# Booster_RF_CH_SUP_CTRL.net
KiCad netlist of a schematic drawn in Altium Designer
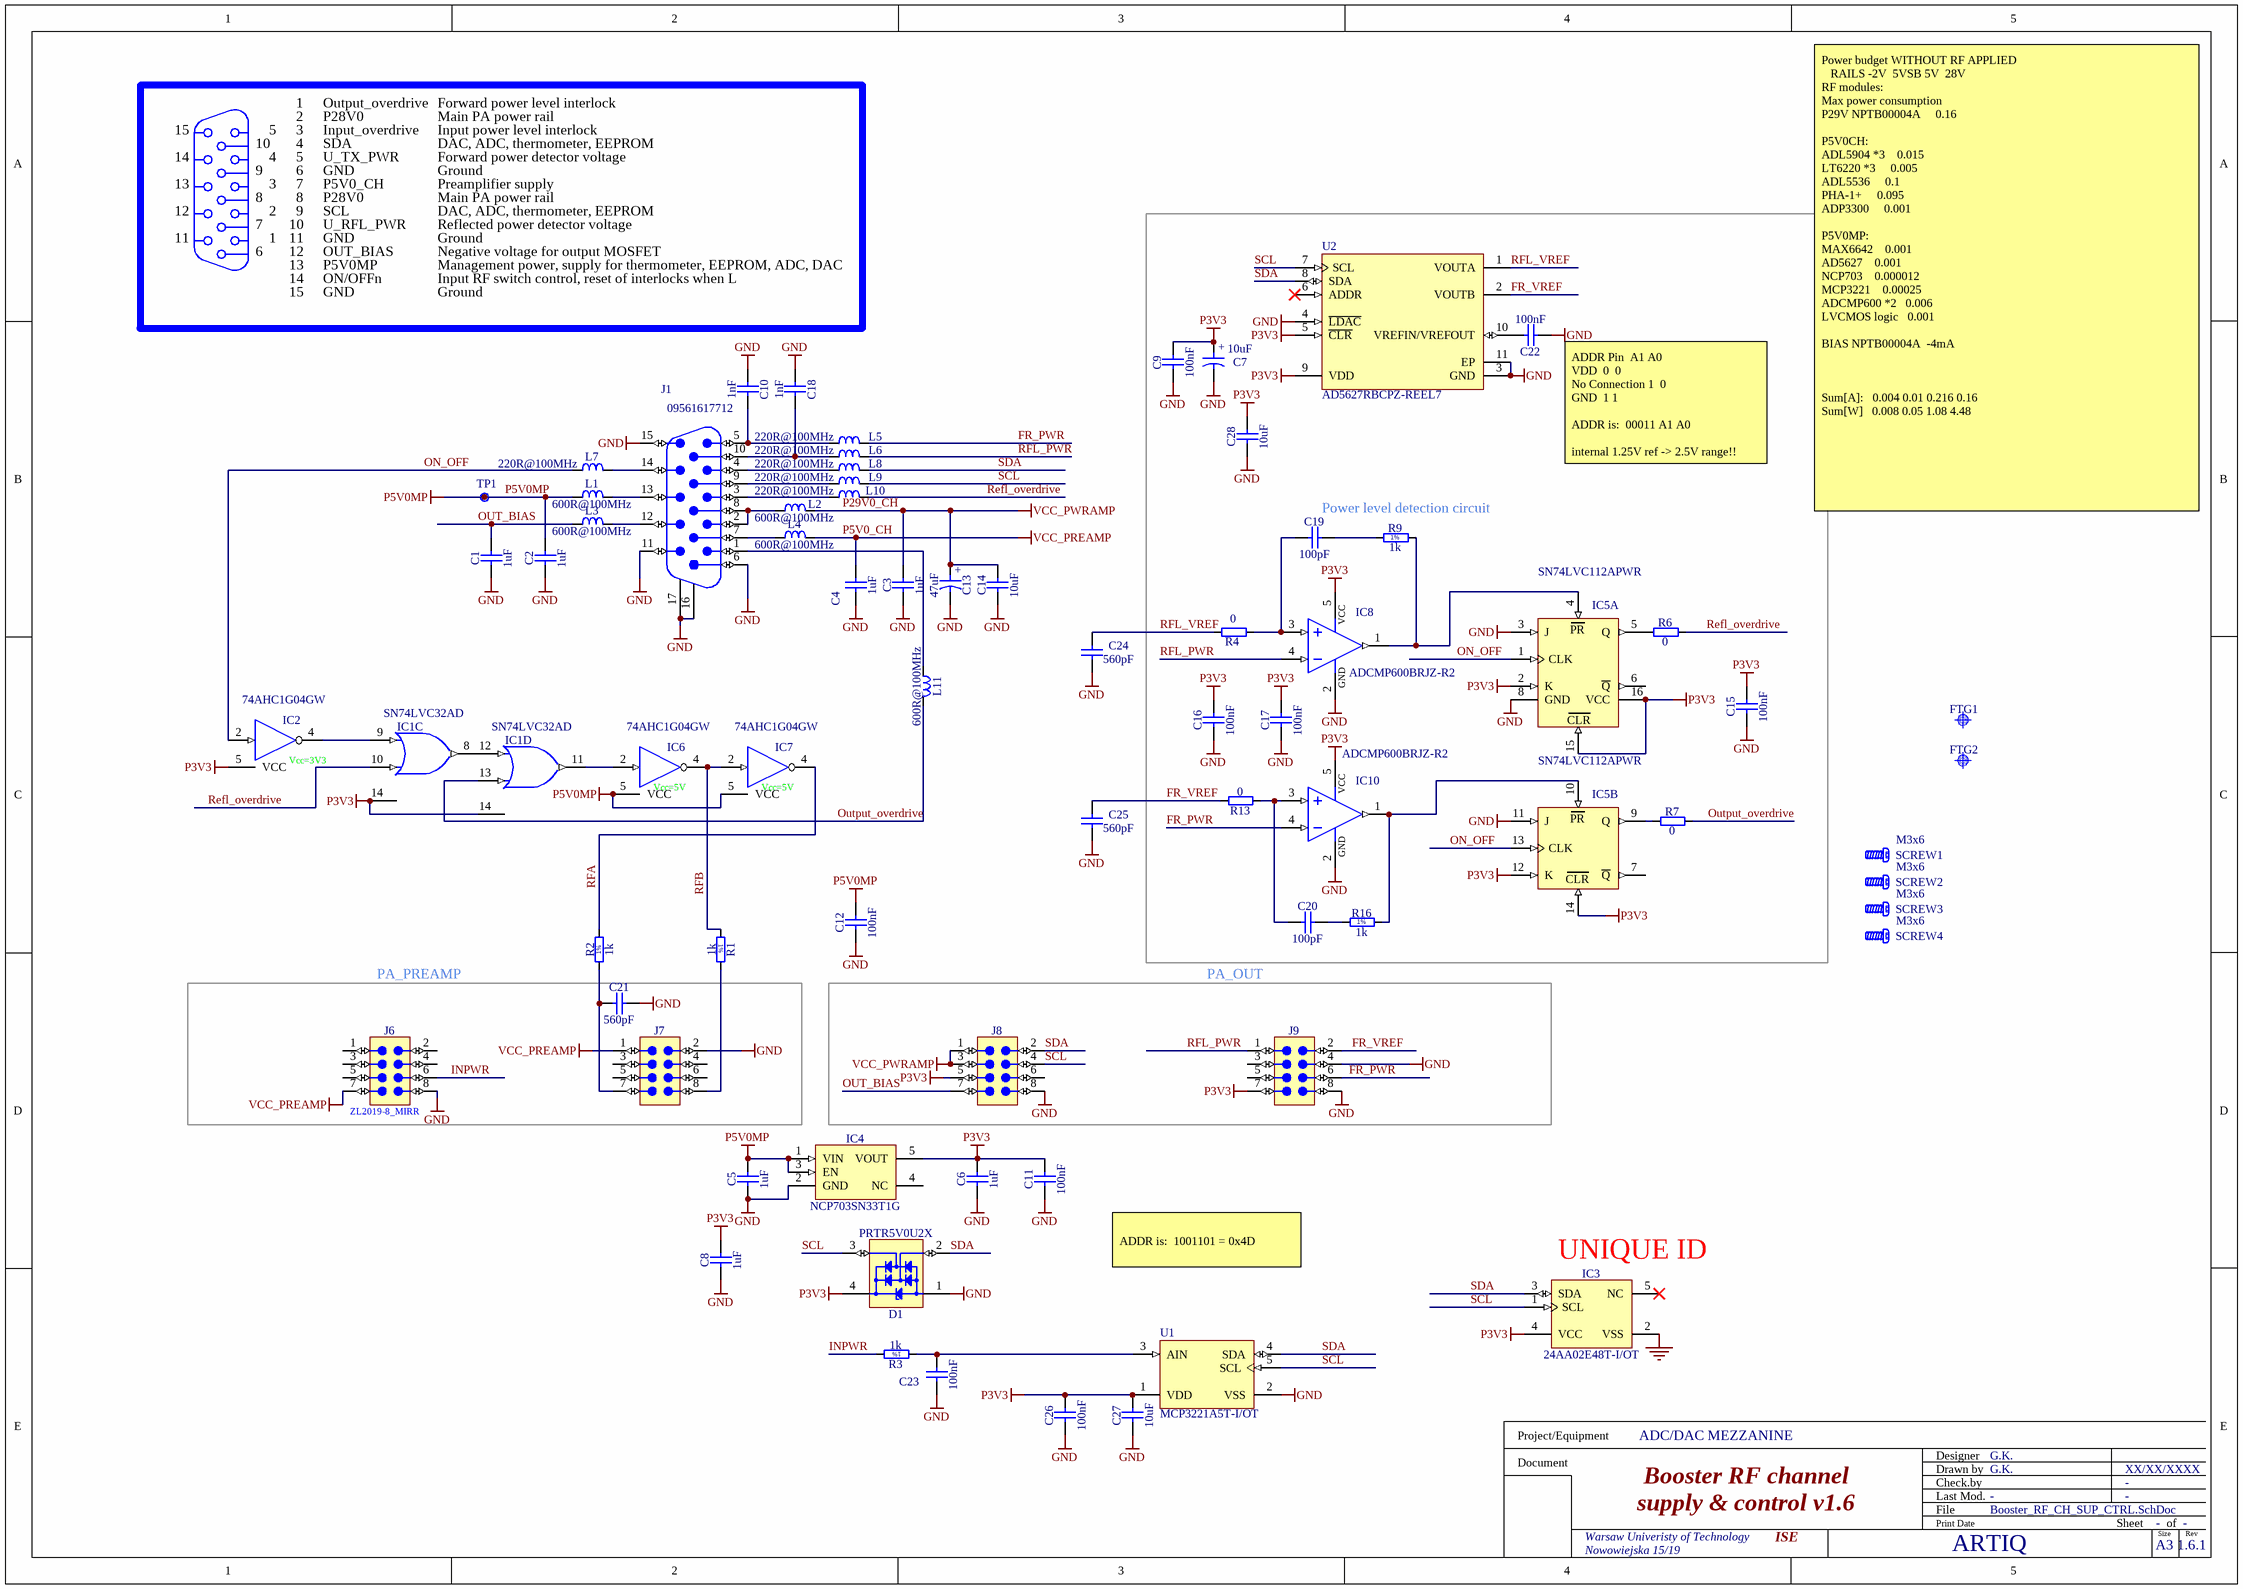
[diagram p0: Booster_RF_CH_SUP_CTRL.SchDoc]

(export (version "E")
  (design (tool "Eeschema 10.0.6"))
  (components
    (comp (ref "C1")
      (value "1uF")
      (footprint "CAPC2012X110N")
      (description "Non-polarised capacitor")
      (fields
        (field (name "PART NUMBER") "CC0805_1UF_50V_10%_X7R")
        (field (name "VOLTAGE") "50V")
        (field (name "AUTHOR") "CERN DEM JLC")
      )
      (libsource (lib "Capacitors") (part "Capacitor - non polarized"))
    )
    (comp (ref "C2")
      (value "1uF")
      (footprint "CAPC2012X110N")
      (description "Non-polarised capacitor")
      (fields
        (field (name "PART NUMBER") "CC0805_1UF_50V_10%_X7R")
        (field (name "VOLTAGE") "50V")
        (field (name "AUTHOR") "CERN DEM JLC")
      )
      (libsource (lib "Capacitors") (part "Capacitor - non polarized"))
    )
    (comp (ref "C3")
      (value "1uF")
      (footprint "CAPC2012X110N")
      (description "Non-polarised capacitor")
      (fields
        (field (name "PART NUMBER") "CC0805_1UF_50V_10%_X7R")
        (field (name "VOLTAGE") "50V")
        (field (name "AUTHOR") "CERN DEM JLC")
      )
      (libsource (lib "Capacitors") (part "Capacitor - non polarized"))
    )
    (comp (ref "C4")
      (value "1uF")
      (footprint "CAPC2012X110N")
      (description "Non-polarised capacitor")
      (fields
        (field (name "PART NUMBER") "CC0805_1UF_50V_10%_X7R")
        (field (name "VOLTAGE") "50V")
        (field (name "AUTHOR") "CERN DEM JLC")
      )
      (libsource (lib "Capacitors") (part "Capacitor - non polarized"))
    )
    (comp (ref "C5")
      (value "1uF")
      (footprint "CAPC2012X140N")
      (description "Non-polarised capacitor")
      (fields
        (field (name "PART NUMBER") "CC0805_1UF_35V_20%_X7R")
        (field (name "VOLTAGE") "35V")
        (field (name "AUTHOR") "CERN DEM JLC")
      )
      (libsource (lib "Capacitors") (part "Capacitor - non polarized"))
    )
    (comp (ref "C6")
      (value "1uF")
      (footprint "CAPC2012X140N")
      (description "Non-polarised capacitor")
      (fields
        (field (name "PART NUMBER") "CC0805_1UF_35V_20%_X7R")
        (field (name "VOLTAGE") "35V")
        (field (name "AUTHOR") "CERN DEM JLC")
      )
      (libsource (lib "Capacitors") (part "Capacitor - non polarized"))
    )
    (comp (ref "C7")
      (value "10uF")
      (footprint "CAPMP3216X180N")
      (description "Polarised capacitor")
      (fields
        (field (name "PART NUMBER") "CTE3216-18_10UF_16V_20%_AVX_TCJ")
        (field (name "VOLTAGE") "16V")
        (field (name "AUTHOR") "CERN DEM JLC")
      )
      (libsource (lib "Capacitors") (part "Capacitor - polarized"))
    )
    (comp (ref "C8")
      (value "1uF")
      (footprint "CAPC2012X140N")
      (description "Non-polarised capacitor")
      (fields
        (field (name "PART NUMBER") "CC0805_1UF_35V_20%_X7R")
        (field (name "VOLTAGE") "35V")
        (field (name "AUTHOR") "CERN DEM JLC")
      )
      (libsource (lib "Capacitors") (part "Capacitor - non polarized"))
    )
    (comp (ref "C9")
      (value "100nF")
      (footprint "CAPC1005X55N")
      (description "Non-polarised capacitor")
      (fields
        (field (name "PART NUMBER") "CC0402_100NF_16V_10%_X5R")
        (field (name "VOLTAGE") "16V")
        (field (name "AUTHOR") "CERN DEM JLC")
      )
      (libsource (lib "Capacitors") (part "Capacitor - non polarized"))
    )
    (comp (ref "C10")
      (value "1nF")
      (footprint "CAPC1608X90N")
      (description "Non-polarised capacitor")
      (fields
        (field (name "PART NUMBER") "CC0603_1NF_50V_5%_NP0")
        (field (name "VOLTAGE") "50V")
        (field (name "AUTHOR") "CERN DEM JLC")
      )
      (libsource (lib "Capacitors") (part "Capacitor - non polarized"))
    )
    (comp (ref "C11")
      (value "100nF")
      (footprint "CAPC1005X55N")
      (description "Non-polarised capacitor")
      (fields
        (field (name "PART NUMBER") "CC0402_100NF_16V_10%_X5R")
        (field (name "VOLTAGE") "16V")
        (field (name "AUTHOR") "CERN DEM JLC")
      )
      (libsource (lib "Capacitors") (part "Capacitor - non polarized"))
    )
    (comp (ref "C12")
      (value "100nF")
      (footprint "CAPC1005X55N")
      (description "Non-polarised capacitor")
      (fields
        (field (name "PART NUMBER") "CC0402_100NF_16V_10%_X5R")
        (field (name "VOLTAGE") "16V")
        (field (name "AUTHOR") "CERN DEM JLC")
      )
      (libsource (lib "Capacitors") (part "Capacitor - non polarized"))
    )
    (comp (ref "C13")
      (value "47uF")
      (footprint "CAPMP7343X430N")
      (description "Polarised capacitor")
      (fields
        (field (name "PART NUMBER") "CTE7343-43_47UF_35V_10%_LESR0300")
        (field (name "VOLTAGE") "35V")
        (field (name "AUTHOR") "CERN DEM JLC")
      )
      (libsource (lib "Capacitors") (part "Capacitor - polarized"))
    )
    (comp (ref "C14")
      (value "10uF")
      (footprint "CAPC3216X190N")
      (description "Non-polarised capacitor")
      (fields
        (field (name "PART NUMBER") "CC1206_10UF_50V_10%_X5R_TDK_CGA5L3X5R1H106K160AB")
        (field (name "VOLTAGE") "50V")
        (field (name "AUTHOR") "CERN DEM BC")
      )
      (libsource (lib "Capacitors") (part "Capacitor - non polarized"))
    )
    (comp (ref "C15")
      (value "100nF")
      (footprint "CAPC1005X55N")
      (description "Non-polarised capacitor")
      (fields
        (field (name "PART NUMBER") "CC0402_100NF_16V_10%_X5R")
        (field (name "VOLTAGE") "16V")
        (field (name "AUTHOR") "CERN DEM JLC")
      )
      (libsource (lib "Capacitors") (part "Capacitor - non polarized"))
    )
    (comp (ref "C16")
      (value "100nF")
      (footprint "CAPC1005X55N")
      (description "Non-polarised capacitor")
      (fields
        (field (name "PART NUMBER") "CC0402_100NF_16V_10%_X5R")
        (field (name "VOLTAGE") "16V")
        (field (name "AUTHOR") "CERN DEM JLC")
      )
      (libsource (lib "Capacitors") (part "Capacitor - non polarized"))
    )
    (comp (ref "C17")
      (value "100nF")
      (footprint "CAPC1005X55N")
      (description "Non-polarised capacitor")
      (fields
        (field (name "PART NUMBER") "CC0402_100NF_16V_10%_X5R")
        (field (name "VOLTAGE") "16V")
        (field (name "AUTHOR") "CERN DEM JLC")
      )
      (libsource (lib "Capacitors") (part "Capacitor - non polarized"))
    )
    (comp (ref "C18")
      (value "1nF")
      (footprint "CAPC1608X90N")
      (description "Non-polarised capacitor")
      (fields
        (field (name "PART NUMBER") "CC0603_1NF_50V_5%_NP0")
        (field (name "VOLTAGE") "50V")
        (field (name "AUTHOR") "CERN DEM JLC")
      )
      (libsource (lib "Capacitors") (part "Capacitor - non polarized"))
    )
    (comp (ref "C19")
      (value "100pF")
      (footprint "CAPC1005X55N")
      (description "Non-polarised capacitor")
      (fields
        (field (name "PART NUMBER") "CC0402_100PF_50V_5%_C0G")
        (field (name "VOLTAGE") "50V")
        (field (name "AUTHOR") "CERN DEM JLC")
      )
      (libsource (lib "Capacitors") (part "Capacitor - non polarized"))
    )
    (comp (ref "C20")
      (value "100pF")
      (footprint "CAPC1005X55N")
      (description "Non-polarised capacitor")
      (fields
        (field (name "PART NUMBER") "CC0402_100PF_50V_5%_C0G")
        (field (name "VOLTAGE") "50V")
        (field (name "AUTHOR") "CERN DEM JLC")
      )
      (libsource (lib "Capacitors") (part "Capacitor - non polarized"))
    )
    (comp (ref "C21")
      (value "560pF")
      (footprint "CAPC1608X87N")
      (description "Non-polarised capacitor")
      (fields
        (field (name "PART NUMBER") "CC0603_560PF_50V_5%_NP0")
        (field (name "VOLTAGE") "50V")
        (field (name "AUTHOR") "CERN DEM JLC")
      )
      (libsource (lib "Capacitors") (part "Capacitor - non polarized"))
    )
    (comp (ref "C22")
      (value "100nF")
      (footprint "CAPC1005X55N")
      (description "Non-polarised capacitor")
      (fields
        (field (name "PART NUMBER") "CC0402_100NF_16V_10%_X5R")
        (field (name "VOLTAGE") "16V")
        (field (name "AUTHOR") "CERN DEM JLC")
      )
      (libsource (lib "Capacitors") (part "Capacitor - non polarized"))
    )
    (comp (ref "C23")
      (value "100nF")
      (footprint "CAPC1005X55N")
      (description "Non-polarised capacitor")
      (fields
        (field (name "PART NUMBER") "CC0402_100NF_16V_10%_X5R")
        (field (name "VOLTAGE") "16V")
        (field (name "AUTHOR") "CERN DEM JLC")
      )
      (libsource (lib "Capacitors") (part "Capacitor - non polarized"))
    )
    (comp (ref "C24")
      (value "560pF")
      (footprint "CAPC1608X87N")
      (description "Non-polarised capacitor")
      (fields
        (field (name "PART NUMBER") "CC0603_560PF_50V_5%_NP0")
        (field (name "VOLTAGE") "50V")
        (field (name "AUTHOR") "CERN DEM JLC")
      )
      (libsource (lib "Capacitors") (part "Capacitor - non polarized"))
    )
    (comp (ref "C25")
      (value "560pF")
      (footprint "CAPC1608X87N")
      (description "Non-polarised capacitor")
      (fields
        (field (name "PART NUMBER") "CC0603_560PF_50V_5%_NP0")
        (field (name "VOLTAGE") "50V")
        (field (name "AUTHOR") "CERN DEM JLC")
      )
      (libsource (lib "Capacitors") (part "Capacitor - non polarized"))
    )
    (comp (ref "C26")
      (value "100nF")
      (footprint "CAPC1005X55N")
      (description "Non-polarised capacitor")
      (fields
        (field (name "PART NUMBER") "CC0402_100NF_16V_10%_X5R")
        (field (name "VOLTAGE") "16V")
        (field (name "AUTHOR") "CERN DEM JLC")
      )
      (libsource (lib "Capacitors") (part "Capacitor - non polarized"))
    )
    (comp (ref "C27")
      (value "10uF")
      (footprint "CAPC3216X190N")
      (description "Non-polarised capacitor")
      (fields
        (field (name "PART NUMBER") "CC1206_10UF_50V_10%_X5R_TDK_CGA5L3X5R1H106K160AB")
        (field (name "VOLTAGE") "50V")
        (field (name "AUTHOR") "CERN DEM BC")
      )
      (libsource (lib "Capacitors") (part "Capacitor - non polarized"))
    )
    (comp (ref "C28")
      (value "10uF")
      (footprint "CAPC3216X190N")
      (description "Non-polarised capacitor")
      (fields
        (field (name "PART NUMBER") "CC1206_10UF_50V_10%_X5R_TDK_CGA5L3X5R1H106K160AB")
        (field (name "VOLTAGE") "50V")
        (field (name "AUTHOR") "CERN DEM BC")
      )
      (libsource (lib "Capacitors") (part "Capacitor - non polarized"))
    )
    (comp (ref "D1")
      (value "PRTR5V0U2X")
      (footprint "SOT190P230X110-4N")
      (description "Ultra Low Capacitance Double Rail-to-Rail ESD Protection Diode")
      (fields
        (field (name "VOLTAGE") "5.5V")
        (field (name "MANUFACTURER") "NXP SEMICONDUCTORS")
        (field (name "AUTHOR") "CERN DEM JLC")
      )
      (libsource (lib "ICs And Semiconductors") (part "PRTR5V0U2X"))
    )
    (comp (ref "FTG1")
      (value "Use only in PCB")
      (footprint "FIDUCIAL_TOP_C100-200")
      (description "Fiducial Target")
      (fields (field (name "PART NUMBER") "FIDUCIAL_TARGET_C100-200") (field (name "AUTHOR") "CERN DEM JLC"))
      (libsource (lib "Eletro-mechanical") (part "Fiducial Target"))
    )
    (comp (ref "FTG2")
      (value "Use only in PCB")
      (footprint "FIDUCIAL_TOP_S100-200")
      (description "Fiducial Target")
      (fields (field (name "PART NUMBER") "FIDUCIAL_TARGET_S100-200") (field (name "AUTHOR") "CERN DEM JLC"))
      (libsource (lib "Eletro-mechanical") (part "Fiducial Target"))
    )
    (comp (ref "IC1")
      (value "SN74LVC32AD")
      (footprint "SOIC127P600X175-14N")
      (description "Quad 2-Input OR Gate")
      (fields (field (name "MANUFACTURER") "TEXAS INSTRUMENTS") (field (name "AUTHOR") "CERN DEM JLC"))
      (libsource (lib "ICs And Semiconductors") (part "7432"))
    )
    (comp (ref "IC2")
      (value "74AHC1G04GW")
      (footprint "SOT65P212X110-5N")
      (description "Single Inverter Buffer")
      (fields (field (name "MANUFACTURER") "NXP SEMICONDUCTORS") (field (name "AUTHOR") "CERN DEM JLC"))
      (libsource (lib "ICs And Semiconductors") (part "741G04"))
    )
    (comp (ref "IC3")
      (value "24AA02E48T-I/OT")
      (footprint "SOT95P280X145-5N")
      (description "1.7V-5.5V, 2K I2C Serial EEPROM With EUI-48 Node Identity")
      (fields (field (name "MANUFACTURER") "MICROCHIP TECHNOLOGY") (field (name "AUTHOR") "CERN DEM MR"))
      (libsource (lib "ICs And Semiconductors") (part "24AA02E48T-I/OT"))
    )
    (comp (ref "IC4")
      (value "NCP703SN33T1G")
      (footprint "SOT95P275X110-5N")
      (description "3.3V 300mA, Ultra-Low Quiescent Current, IQ 12uA, Ultra-Low Noise, LDO Voltage Regulator")
      (fields (field (name "MANUFACTURER") "ON SEMICONDUCTOR") (field (name "AUTHOR") "CERN DEM JLC"))
      (libsource (lib "ICs And Semiconductors") (part "NCP703SN"))
    )
    (comp (ref "IC5")
      (value "SN74LVC112APWR")
      (footprint "SOP65P640X120-16N")
      (description "Dual Negative-Edge-Triggered J-K Flip-Flop With Clear And Preset")
      (fields (field (name "MANUFACTURER") "TEXAS INSTRUMENTS") (field (name "AUTHOR") "CERN DEM JLC"))
      (libsource (lib "ICS-logic") (part "74LVC112APWR"))
    )
    (comp (ref "IC6")
      (value "74AHC1G04GW")
      (footprint "SOT65P212X110-5N")
      (description "Single Inverter Buffer")
      (fields (field (name "MANUFACTURER") "NXP SEMICONDUCTORS") (field (name "AUTHOR") "CERN DEM JLC"))
      (libsource (lib "ICs And Semiconductors") (part "741G04"))
    )
    (comp (ref "IC7")
      (value "74AHC1G04GW")
      (footprint "SOT65P212X110-5N")
      (description "Single Inverter Buffer")
      (fields (field (name "MANUFACTURER") "NXP SEMICONDUCTORS") (field (name "AUTHOR") "CERN DEM JLC"))
      (libsource (lib "ICs And Semiconductors") (part "741G04"))
    )
    (comp (ref "IC8")
      (value "ADCMP600BRJZ-R2")
      (footprint "SOT95P280X145-5N")
      (description "Rail-to-Rail, Very Fast, 2.5 V to 5.5 V Single-Supply TTL/CMOS Comparator")
      (fields (field (name "MANUFACTURER") "ANALOG DEVICES") (field (name "AUTHOR") "CERN DEM JLC"))
      (libsource (lib "ICs And Semiconductors") (part "ADCMP600"))
    )
    (comp (ref "IC10")
      (value "ADCMP600BRJZ-R2")
      (footprint "SOT95P280X145-5N")
      (description "Rail-to-Rail, Very Fast, 2.5 V to 5.5 V Single-Supply TTL/CMOS Comparator")
      (fields (field (name "MANUFACTURER") "ANALOG DEVICES") (field (name "AUTHOR") "CERN DEM JLC"))
      (libsource (lib "ICs And Semiconductors") (part "ADCMP600"))
    )
    (comp (ref "J1")
      (value "HD-Sub")
      (footprint "TYCO_5750489-1")
      (description "Connector High Density D-sub 15 Male")
      (fields
        (field (name "PART NUMBER") "HARTING_09561617712")
        (field (name "MANUFACTURER") "HARTING Elektronik")
        (field (name "MANUFACTURER PART NUMBER") "09561617712")
        (field (name "AUTHOR") "GK")
      )
      (libsource (lib "LIBRARY_SCH") (part "CON_DB15_V_M_5750489-1"))
    )
    (comp (ref "J6")
      (value "Header 8")
      (footprint "ZL2019-8_MIRR")
      (description "Connector 8 Male")
      (fields
        (field (name "PART NUMBER") "ZL2019-8")
        (field (name "MANUFACTURER") "NINIGI")
        (field (name "AUTHOR") "GK")
      )
      (libsource (lib "LIBRARY_SCH") (part "CON_2x4 2.54 male MIRROR"))
    )
    (comp (ref "J7")
      (value "Header 8")
      (footprint "ZL2019-8_MIRR")
      (description "Connector 8 Male")
      (fields
        (field (name "PART NUMBER") "ZL2019-8")
        (field (name "MANUFACTURER") "NINIGI")
        (field (name "AUTHOR") "GK")
      )
      (libsource (lib "LIBRARY_SCH") (part "CON_2x4 2.54 male MIRROR"))
    )
    (comp (ref "J8")
      (value "Header 8")
      (footprint "ZL2019-8_MIRR")
      (description "Connector 8 Male")
      (fields
        (field (name "PART NUMBER") "ZL2019-8")
        (field (name "MANUFACTURER") "NINIGI")
        (field (name "AUTHOR") "GK")
      )
      (libsource (lib "LIBRARY_SCH") (part "CON_2x4 2.54 male MIRROR"))
    )
    (comp (ref "J9")
      (value "Header 8")
      (footprint "ZL2019-8_MIRR")
      (description "Connector 8 Male")
      (fields
        (field (name "PART NUMBER") "ZL2019-8")
        (field (name "MANUFACTURER") "NINIGI")
        (field (name "AUTHOR") "GK")
      )
      (libsource (lib "LIBRARY_SCH") (part "CON_2x4 2.54 male MIRROR"))
    )
    (comp (ref "L1")
      (value "600R@100MHz")
      (footprint "INDC3216X130N")
      (description "Inductor")
      (fields
        (field (name "PART NUMBER") "IND1206_WURTH_74279218")
        (field (name "POWER") "2A")
        (field (name "AUTHOR") "CERN DEM JLC")
      )
      (libsource (lib "Inductors & Transformers") (part "Inductor"))
    )
    (comp (ref "L2")
      (value "600R@100MHz")
      (footprint "INDC3216X130N")
      (description "Inductor")
      (fields
        (field (name "PART NUMBER") "IND1206_WURTH_74279218")
        (field (name "POWER") "2A")
        (field (name "AUTHOR") "CERN DEM JLC")
      )
      (libsource (lib "Inductors & Transformers") (part "Inductor"))
    )
    (comp (ref "L3")
      (value "600R@100MHz")
      (footprint "INDC3216X130N")
      (description "Inductor")
      (fields
        (field (name "PART NUMBER") "IND1206_WURTH_74279218")
        (field (name "POWER") "2A")
        (field (name "AUTHOR") "CERN DEM JLC")
      )
      (libsource (lib "Inductors & Transformers") (part "Inductor"))
    )
    (comp (ref "L4")
      (value "600R@100MHz")
      (footprint "INDC3216X130N")
      (description "Inductor")
      (fields
        (field (name "PART NUMBER") "IND1206_WURTH_74279218")
        (field (name "POWER") "2A")
        (field (name "AUTHOR") "CERN DEM JLC")
      )
      (libsource (lib "Inductors & Transformers") (part "Inductor"))
    )
    (comp (ref "L5")
      (value "220R@100MHz")
      (footprint "INDC1005X55N")
      (description "Inductor")
      (fields
        (field (name "PART NUMBER") "IND0402_MURATA_BLM15HB221SN1")
        (field (name "POWER") "250mA")
        (field (name "AUTHOR") "CERN DEM JLC")
      )
      (libsource (lib "Inductors & Transformers") (part "Inductor"))
    )
    (comp (ref "L6")
      (value "220R@100MHz")
      (footprint "INDC1005X55N")
      (description "Inductor")
      (fields
        (field (name "PART NUMBER") "IND0402_MURATA_BLM15HB221SN1")
        (field (name "POWER") "250mA")
        (field (name "AUTHOR") "CERN DEM JLC")
      )
      (libsource (lib "Inductors & Transformers") (part "Inductor"))
    )
    (comp (ref "L7")
      (value "220R@100MHz")
      (footprint "INDC1005X55N")
      (description "Inductor")
      (fields
        (field (name "PART NUMBER") "IND0402_MURATA_BLM15HB221SN1")
        (field (name "POWER") "250mA")
        (field (name "AUTHOR") "CERN DEM JLC")
      )
      (libsource (lib "Inductors & Transformers") (part "Inductor"))
    )
    (comp (ref "L8")
      (value "220R@100MHz")
      (footprint "INDC1005X55N")
      (description "Inductor")
      (fields
        (field (name "PART NUMBER") "IND0402_MURATA_BLM15HB221SN1")
        (field (name "POWER") "250mA")
        (field (name "AUTHOR") "CERN DEM JLC")
      )
      (libsource (lib "Inductors & Transformers") (part "Inductor"))
    )
    (comp (ref "L9")
      (value "220R@100MHz")
      (footprint "INDC1005X55N")
      (description "Inductor")
      (fields
        (field (name "PART NUMBER") "IND0402_MURATA_BLM15HB221SN1")
        (field (name "POWER") "250mA")
        (field (name "AUTHOR") "CERN DEM JLC")
      )
      (libsource (lib "Inductors & Transformers") (part "Inductor"))
    )
    (comp (ref "L10")
      (value "220R@100MHz")
      (footprint "INDC1005X55N")
      (description "Inductor")
      (fields
        (field (name "PART NUMBER") "IND0402_MURATA_BLM15HB221SN1")
        (field (name "POWER") "250mA")
        (field (name "AUTHOR") "CERN DEM JLC")
      )
      (libsource (lib "Inductors & Transformers") (part "Inductor"))
    )
    (comp (ref "L11")
      (value "600R@100MHz")
      (footprint "INDC3216X130N")
      (description "Inductor")
      (fields
        (field (name "PART NUMBER") "IND1206_WURTH_74279218")
        (field (name "POWER") "2A")
        (field (name "AUTHOR") "CERN DEM JLC")
      )
      (libsource (lib "") (part "Inductor_1"))
    )
    (comp (ref "R1")
      (value "1k")
      (footprint "RESC1005X40N")
      (description "Resistor - 1%")
      (fields
        (field (name "PART NUMBER") "R0402_1K_1%_0.0625W_100PPM")
        (field (name "POWER") "0.0625W")
        (field (name "AUTHOR") "CERN DEM JLC")
      )
      (libsource (lib "Resistors") (part "Resistor - 1%"))
    )
    (comp (ref "R2")
      (value "1k")
      (footprint "RESC1005X40N")
      (description "Resistor - 1%")
      (fields
        (field (name "PART NUMBER") "R0402_1K_1%_0.0625W_100PPM")
        (field (name "POWER") "0.0625W")
        (field (name "AUTHOR") "CERN DEM JLC")
      )
      (libsource (lib "Resistors") (part "Resistor - 1%"))
    )
    (comp (ref "R3")
      (value "1k")
      (footprint "RESC1005X40N")
      (description "Resistor - 1%")
      (fields
        (field (name "PART NUMBER") "R0402_1K_1%_0.0625W_100PPM")
        (field (name "POWER") "0.0625W")
        (field (name "AUTHOR") "CERN DEM JLC")
      )
      (libsource (lib "Resistors") (part "Resistor - 1%"))
    )
    (comp (ref "R4")
      (value "0")
      (footprint "RESC1005X40N")
      (description "Resistor")
      (fields
        (field (name "PART NUMBER") "R0402_0R_JUMPER")
        (field (name "MANUFACTURER") "GENERIC")
        (field (name "AUTHOR") "CERN DEM JLC")
      )
      (libsource (lib "Resistors") (part "Resistor"))
    )
    (comp (ref "R6")
      (value "0")
      (footprint "RESC1608X55N")
      (description "Resistor")
      (fields
        (field (name "PART NUMBER") "R0603_0R_JUMPER")
        (field (name "MANUFACTURER") "GENERIC")
        (field (name "AUTHOR") "CERN DEM JLC")
      )
      (libsource (lib "Resistors") (part "Resistor"))
    )
    (comp (ref "R7")
      (value "0")
      (footprint "RESC1608X55N")
      (description "Resistor")
      (fields
        (field (name "PART NUMBER") "R0603_0R_JUMPER")
        (field (name "MANUFACTURER") "GENERIC")
        (field (name "AUTHOR") "CERN DEM JLC")
      )
      (libsource (lib "Resistors") (part "Resistor"))
    )
    (comp (ref "R9")
      (value "1k")
      (footprint "RESC1005X40N")
      (description "Resistor - 1%")
      (fields
        (field (name "PART NUMBER") "R0402_1K_1%_0.0625W_100PPM")
        (field (name "POWER") "0.0625W")
        (field (name "AUTHOR") "CERN DEM JLC")
      )
      (libsource (lib "Resistors") (part "Resistor - 1%"))
    )
    (comp (ref "R13")
      (value "0")
      (footprint "RESC1005X40N")
      (description "Resistor")
      (fields
        (field (name "PART NUMBER") "R0402_0R_JUMPER")
        (field (name "MANUFACTURER") "GENERIC")
        (field (name "AUTHOR") "CERN DEM JLC")
      )
      (libsource (lib "Resistors") (part "Resistor"))
    )
    (comp (ref "R16")
      (value "1k")
      (footprint "RESC1005X40N")
      (description "Resistor - 1%")
      (fields
        (field (name "PART NUMBER") "R0402_1K_1%_0.0625W_100PPM")
        (field (name "POWER") "0.0625W")
        (field (name "AUTHOR") "CERN DEM JLC")
      )
      (libsource (lib "Resistors") (part "Resistor - 1%"))
    )
    (comp (ref "SCREW1")
      (value "M3x6")
      (footprint "BOSSARD_BN5687-3061605_v")
      (description "Screw")
      (fields
        (field (name "PART NUMBER") "BOSSARD_BN5687-3061605_v")
        (field (name "MANUFACTURER") "BOSSARD")
        (field (name "AUTHOR") "CERN DEM JLC")
      )
      (libsource (lib "Eletro-mechanical") (part "Screw"))
    )
    (comp (ref "SCREW2")
      (value "M3x6")
      (footprint "BOSSARD_BN5687-3061605_v")
      (description "Screw")
      (fields
        (field (name "PART NUMBER") "BOSSARD_BN5687-3061605_v")
        (field (name "MANUFACTURER") "BOSSARD")
        (field (name "AUTHOR") "CERN DEM JLC")
      )
      (libsource (lib "Eletro-mechanical") (part "Screw"))
    )
    (comp (ref "SCREW3")
      (value "M3x6")
      (footprint "BOSSARD_BN5687-3061605_v")
      (description "Screw")
      (fields
        (field (name "PART NUMBER") "BOSSARD_BN5687-3061605_v")
        (field (name "MANUFACTURER") "BOSSARD")
        (field (name "AUTHOR") "CERN DEM JLC")
      )
      (libsource (lib "Eletro-mechanical") (part "Screw"))
    )
    (comp (ref "SCREW4")
      (value "M3x6")
      (footprint "BOSSARD_BN5687-3061605_v")
      (description "Screw")
      (fields
        (field (name "PART NUMBER") "BOSSARD_BN5687-3061605_v")
        (field (name "MANUFACTURER") "BOSSARD")
        (field (name "AUTHOR") "CERN DEM JLC")
      )
      (libsource (lib "Eletro-mechanical") (part "Screw"))
    )
    (comp (ref "TP1")
      (value "Test Point")
      (footprint "TPS127")
      (fields (field (name "PART NUMBER") "SMD_PAD_1.27X1.27MM") (field (name "AUTHOR") "CERN DEM JLC"))
      (libsource (lib "Eletro-mechanical") (part "Test Point"))
    )
    (comp (ref "U1")
      (value "MCP3221A5T-I/OT")
      (footprint "SOT-23-OT5_L")
      (libsource (lib "Altium Content Vault") (part "CON-ADC-MCP3021-5"))
    )
    (comp (ref "U2")
      (value "AD5627RBCPZ-REEL7")
      (footprint "CP-10-9_M")
      (fields (field (name "MANUFACTURER") "Analog Devices") (field (name "GENERIC PART NUMBER") "AD5627R"))
      (libsource (lib "Altium Content Vault") (part "ADI-AD5627R-CP-10-9"))
    )
  )
  (nets
    (net (code "1") (name "/FR_PWR") (class "Default")
      (node (ref "IC10") (pin "4") (pinfunction "VN_4") (pintype "input"))
      (node (ref "J9") (pin "6") (pinfunction "6_6") (pintype "bidirectional"))
      (node (ref "L5") (pin "2") (pinfunction "2_2") (pintype "passive"))
    )
    (net (code "2") (name "/FR_VREF") (class "Default")
      (node (ref "C25") (pin "1") (pinfunction "1_1") (pintype "passive"))
      (node (ref "J9") (pin "2") (pinfunction "2_2") (pintype "bidirectional"))
      (node (ref "R13") (pin "2") (pinfunction "2_2") (pintype "passive"))
      (node (ref "U2") (pin "2") (pinfunction "VOUTB_2") (pintype "tri_state"))
    )
    (net (code "3") (name "/INPWR") (class "Default")
      (node (ref "J6") (pin "6") (pinfunction "6_6") (pintype "bidirectional"))
      (node (ref "R3") (pin "2") (pinfunction "2_2") (pintype "passive"))
    )
    (net (code "4") (name "/ON_OFF") (class "Default")
      (node (ref "IC2") (pin "2") (pinfunction "IN_2") (pintype "input"))
      (node (ref "IC5") (pin "1") (pinfunction "CLK_1") (pintype "input"))
      (node (ref "IC5") (pin "13") (pinfunction "CLK_13") (pintype "input"))
      (node (ref "L7") (pin "1") (pinfunction "1_1") (pintype "passive"))
    )
    (net (code "5") (name "/OUT_BIAS") (class "Default")
      (node (ref "C1") (pin "2") (pinfunction "2_2") (pintype "passive"))
      (node (ref "J8") (pin "7") (pinfunction "7_7") (pintype "bidirectional"))
      (node (ref "L3") (pin "1") (pinfunction "1_1") (pintype "passive"))
    )
    (net (code "6") (name "/Output_overdrive") (class "Default")
      (node (ref "IC1") (pin "13") (pinfunction "B_13") (pintype "input"))
      (node (ref "L11") (pin "2") (pinfunction "2_2") (pintype "passive"))
      (node (ref "R7") (pin "2") (pinfunction "2_2") (pintype "passive"))
    )
    (net (code "7") (name "/RFA") (class "Default")
      (node (ref "IC7") (pin "4") (pinfunction "OUT_4") (pintype "open_collector"))
      (node (ref "R2") (pin "2") (pinfunction "2_2") (pintype "passive"))
    )
    (net (code "8") (name "/RFB") (class "Default")
      (node (ref "IC6") (pin "4") (pinfunction "OUT_4") (pintype "open_collector"))
      (node (ref "IC7") (pin "2") (pinfunction "IN_2") (pintype "input"))
      (node (ref "R1") (pin "1") (pinfunction "1_1") (pintype "passive"))
    )
    (net (code "9") (name "/RFL_PWR") (class "Default")
      (node (ref "IC8") (pin "4") (pinfunction "VN_4") (pintype "input"))
      (node (ref "J9") (pin "1") (pinfunction "1_1") (pintype "bidirectional"))
      (node (ref "L6") (pin "2") (pinfunction "2_2") (pintype "passive"))
    )
    (net (code "10") (name "/RFL_VREF") (class "Default")
      (node (ref "C24") (pin "1") (pinfunction "1_1") (pintype "passive"))
      (node (ref "R4") (pin "2") (pinfunction "2_2") (pintype "passive"))
      (node (ref "U2") (pin "1") (pinfunction "VOUTA_1") (pintype "tri_state"))
    )
    (net (code "11") (name "/Refl_overdrive") (class "Default")
      (node (ref "IC1") (pin "10") (pinfunction "B_10") (pintype "input"))
      (node (ref "L10") (pin "2") (pinfunction "2_2") (pintype "passive"))
      (node (ref "R6") (pin "2") (pinfunction "2_2") (pintype "passive"))
    )
    (net (code "12") (name "/SCL") (class "Default")
      (node (ref "D1") (pin "3") (pinfunction "I/O2_3") (pintype "bidirectional"))
      (node (ref "IC3") (pin "1") (pinfunction "SCL_1") (pintype "input"))
      (node (ref "J8") (pin "4") (pinfunction "4_4") (pintype "bidirectional"))
      (node (ref "L9") (pin "2") (pinfunction "2_2") (pintype "passive"))
      (node (ref "U1") (pin "5") (pinfunction "SCL_5") (pintype "input"))
      (node (ref "U2") (pin "7") (pinfunction "SCL_7") (pintype "input"))
    )
    (net (code "13") (name "/SDA") (class "Default")
      (node (ref "D1") (pin "2") (pinfunction "I/O1_2") (pintype "bidirectional"))
      (node (ref "IC3") (pin "3") (pinfunction "SDA_3") (pintype "bidirectional"))
      (node (ref "J8") (pin "2") (pinfunction "2_2") (pintype "bidirectional"))
      (node (ref "L8") (pin "2") (pinfunction "2_2") (pintype "passive"))
      (node (ref "U1") (pin "4") (pinfunction "SDA_4") (pintype "bidirectional"))
      (node (ref "U2") (pin "8") (pinfunction "SDA_8") (pintype "bidirectional"))
    )
    (net (code "14") (name "GND") (class "Default")
      (node (ref "C1") (pin "1") (pinfunction "1_1") (pintype "passive"))
      (node (ref "C10") (pin "1") (pinfunction "1_1") (pintype "passive"))
      (node (ref "C11") (pin "1") (pinfunction "1_1") (pintype "passive"))
      (node (ref "C12") (pin "1") (pinfunction "1_1") (pintype "passive"))
      (node (ref "C13") (pin "2") (pinfunction "2_2") (pintype "passive"))
      (node (ref "C14") (pin "1") (pinfunction "1_1") (pintype "passive"))
      (node (ref "C15") (pin "1") (pinfunction "1_1") (pintype "passive"))
      (node (ref "C16") (pin "1") (pinfunction "1_1") (pintype "passive"))
      (node (ref "C17") (pin "1") (pinfunction "1_1") (pintype "passive"))
      (node (ref "C18") (pin "1") (pinfunction "1_1") (pintype "passive"))
      (node (ref "C2") (pin "1") (pinfunction "1_1") (pintype "passive"))
      (node (ref "C21") (pin "2") (pinfunction "2_2") (pintype "passive"))
      (node (ref "C22") (pin "1") (pinfunction "1_1") (pintype "passive"))
      (node (ref "C23") (pin "1") (pinfunction "1_1") (pintype "passive"))
      (node (ref "C24") (pin "2") (pinfunction "2_2") (pintype "passive"))
      (node (ref "C25") (pin "2") (pinfunction "2_2") (pintype "passive"))
      (node (ref "C26") (pin "1") (pinfunction "1_1") (pintype "passive"))
      (node (ref "C27") (pin "1") (pinfunction "1_1") (pintype "passive"))
      (node (ref "C28") (pin "1") (pinfunction "1_1") (pintype "passive"))
      (node (ref "C3") (pin "1") (pinfunction "1_1") (pintype "passive"))
      (node (ref "C4") (pin "1") (pinfunction "1_1") (pintype "passive"))
      (node (ref "C5") (pin "1") (pinfunction "1_1") (pintype "passive"))
      (node (ref "C6") (pin "1") (pinfunction "1_1") (pintype "passive"))
      (node (ref "C7") (pin "2") (pinfunction "2_2") (pintype "passive"))
      (node (ref "C8") (pin "1") (pinfunction "1_1") (pintype "passive"))
      (node (ref "C9") (pin "1") (pinfunction "1_1") (pintype "passive"))
      (node (ref "D1") (pin "1") (pinfunction "GND_1") (pintype "power_in"))
      (node (ref "IC1") (pin "7") (pinfunction "GND_7") (pintype "power_in"))
      (node (ref "IC10") (pin "2") (pinfunction "GND_2") (pintype "power_in"))
      (node (ref "IC2") (pin "3") (pinfunction "GND_3") (pintype "power_in"))
      (node (ref "IC3") (pin "2") (pinfunction "VSS_2") (pintype "power_in"))
      (node (ref "IC4") (pin "2") (pinfunction "GND_2") (pintype "power_in"))
      (node (ref "IC5") (pin "11") (pinfunction "J_11") (pintype "input"))
      (node (ref "IC5") (pin "3") (pinfunction "J_3") (pintype "input"))
      (node (ref "IC5") (pin "8") (pinfunction "GND_8") (pintype "power_in"))
      (node (ref "IC6") (pin "3") (pinfunction "GND_3") (pintype "power_in"))
      (node (ref "IC7") (pin "3") (pinfunction "GND_3") (pintype "power_in"))
      (node (ref "IC8") (pin "2") (pinfunction "GND_2") (pintype "power_in"))
      (node (ref "J1") (pin "11") (pinfunction "11_11") (pintype "bidirectional"))
      (node (ref "J1") (pin "15") (pinfunction "15_15") (pintype "bidirectional"))
      (node (ref "J1") (pin "16") (pinfunction "16_16") (pintype "passive"))
      (node (ref "J1") (pin "17") (pinfunction "17_17") (pintype "passive"))
      (node (ref "J1") (pin "6") (pinfunction "6_6") (pintype "bidirectional"))
      (node (ref "J6") (pin "8") (pinfunction "8_8") (pintype "bidirectional"))
      (node (ref "J7") (pin "2") (pinfunction "2_2") (pintype "bidirectional"))
      (node (ref "J8") (pin "8") (pinfunction "8_8") (pintype "bidirectional"))
      (node (ref "J9") (pin "4") (pinfunction "4_4") (pintype "bidirectional"))
      (node (ref "J9") (pin "8") (pinfunction "8_8") (pintype "bidirectional"))
      (node (ref "U1") (pin "2") (pinfunction "VSS_2") (pintype "power_in"))
      (node (ref "U2") (pin "11") (pinfunction "EP_11") (pintype "passive"))
      (node (ref "U2") (pin "3") (pinfunction "GND_3") (pintype "power_in"))
      (node (ref "U2") (pin "4") (pinfunction "~{LDAC}_4") (pintype "input"))
    )
    (net (code "15") (name "Net-(C10-Pad2)") (class "Default")
      (node (ref "C10") (pin "2") (pinfunction "2_2") (pintype "passive"))
      (node (ref "J1") (pin "5") (pinfunction "5_5") (pintype "bidirectional"))
      (node (ref "L5") (pin "1") (pinfunction "1_1") (pintype "passive"))
    )
    (net (code "16") (name "Net-(C18-Pad2)") (class "Default")
      (node (ref "C18") (pin "2") (pinfunction "2_2") (pintype "passive"))
      (node (ref "J1") (pin "10") (pinfunction "10_10") (pintype "bidirectional"))
      (node (ref "L6") (pin "1") (pinfunction "1_1") (pintype "passive"))
    )
    (net (code "17") (name "Net-(C19-Pad2)") (class "Default")
      (node (ref "C19") (pin "2") (pinfunction "2_2") (pintype "passive"))
      (node (ref "R9") (pin "1") (pinfunction "1_1") (pintype "passive"))
    )
    (net (code "18") (name "Net-(C20-Pad2)") (class "Default")
      (node (ref "C20") (pin "2") (pinfunction "2_2") (pintype "passive"))
      (node (ref "R16") (pin "1") (pinfunction "1_1") (pintype "passive"))
    )
    (net (code "19") (name "Net-(C21-Pad1)") (class "Default")
      (node (ref "C21") (pin "1") (pinfunction "1_1") (pintype "passive"))
      (node (ref "J7") (pin "7") (pinfunction "7_7") (pintype "bidirectional"))
      (node (ref "R2") (pin "1") (pinfunction "1_1") (pintype "passive"))
    )
    (net (code "20") (name "Net-(IC1C-A)") (class "Default")
      (node (ref "IC1") (pin "9") (pinfunction "A_9") (pintype "input"))
      (node (ref "IC2") (pin "4") (pinfunction "OUT_4") (pintype "open_collector"))
    )
    (net (code "21") (name "Net-(IC1C-Y)") (class "Default")
      (node (ref "IC1") (pin "12") (pinfunction "A_12") (pintype "input"))
      (node (ref "IC1") (pin "8") (pinfunction "Y_8") (pintype "output"))
    )
    (net (code "22") (name "Net-(IC1D-Y)") (class "Default")
      (node (ref "IC1") (pin "11") (pinfunction "Y_11") (pintype "output"))
      (node (ref "IC6") (pin "2") (pinfunction "IN_2") (pintype "input"))
    )
    (net (code "23") (name "Net-(IC5A-Q)") (class "Default")
      (node (ref "IC5") (pin "5") (pinfunction "Q_5") (pintype "output"))
      (node (ref "R6") (pin "1") (pinfunction "1_1") (pintype "passive"))
    )
    (net (code "24") (name "Net-(IC5A-~{PRE})") (class "Default")
      (node (ref "IC5") (pin "4") (pinfunction "~{PRE}_4") (pintype "input"))
      (node (ref "IC8") (pin "1") (pinfunction "q_1") (pintype "output"))
      (node (ref "R9") (pin "2") (pinfunction "2_2") (pintype "passive"))
    )
    (net (code "25") (name "Net-(IC5B-Q)") (class "Default")
      (node (ref "IC5") (pin "9") (pinfunction "Q_9") (pintype "output"))
      (node (ref "R7") (pin "1") (pinfunction "1_1") (pintype "passive"))
    )
    (net (code "26") (name "Net-(IC8-VP)") (class "Default")
      (node (ref "C19") (pin "1") (pinfunction "1_1") (pintype "passive"))
      (node (ref "IC8") (pin "3") (pinfunction "VP_3") (pintype "input"))
      (node (ref "R4") (pin "1") (pinfunction "1_1") (pintype "passive"))
    )
    (net (code "27") (name "Net-(IC10-VP)") (class "Default")
      (node (ref "C20") (pin "1") (pinfunction "1_1") (pintype "passive"))
      (node (ref "IC10") (pin "3") (pinfunction "VP_3") (pintype "input"))
      (node (ref "R13") (pin "1") (pinfunction "1_1") (pintype "passive"))
    )
    (net (code "28") (name "Net-(IC10-q)") (class "Default")
      (node (ref "IC10") (pin "1") (pinfunction "q_1") (pintype "output"))
      (node (ref "IC5") (pin "10") (pinfunction "~{PRE}_10") (pintype "input"))
      (node (ref "R16") (pin "2") (pinfunction "2_2") (pintype "passive"))
    )
    (net (code "29") (name "Net-(J1-Pad1)") (class "Default")
      (node (ref "J1") (pin "1") (pinfunction "1_1") (pintype "bidirectional"))
      (node (ref "L11") (pin "1") (pinfunction "1_1") (pintype "passive"))
    )
    (net (code "30") (name "Net-(J1-Pad2)") (class "Default")
      (node (ref "J1") (pin "2") (pinfunction "2_2") (pintype "bidirectional"))
      (node (ref "J1") (pin "8") (pinfunction "8_8") (pintype "bidirectional"))
      (node (ref "L2") (pin "1") (pinfunction "1_1") (pintype "passive"))
    )
    (net (code "31") (name "Net-(J1-Pad3)") (class "Default")
      (node (ref "J1") (pin "3") (pinfunction "3_3") (pintype "bidirectional"))
      (node (ref "L10") (pin "1") (pinfunction "1_1") (pintype "passive"))
    )
    (net (code "32") (name "Net-(J1-Pad4)") (class "Default")
      (node (ref "J1") (pin "4") (pinfunction "4_4") (pintype "bidirectional"))
      (node (ref "L8") (pin "1") (pinfunction "1_1") (pintype "passive"))
    )
    (net (code "33") (name "Net-(J1-Pad7)") (class "Default")
      (node (ref "J1") (pin "7") (pinfunction "7_7") (pintype "bidirectional"))
      (node (ref "L4") (pin "1") (pinfunction "1_1") (pintype "passive"))
    )
    (net (code "34") (name "Net-(J1-Pad9)") (class "Default")
      (node (ref "J1") (pin "9") (pinfunction "9_9") (pintype "bidirectional"))
      (node (ref "L9") (pin "1") (pinfunction "1_1") (pintype "passive"))
    )
    (net (code "35") (name "Net-(J1-Pad12)") (class "Default")
      (node (ref "J1") (pin "12") (pinfunction "12_12") (pintype "bidirectional"))
      (node (ref "L3") (pin "2") (pinfunction "2_2") (pintype "passive"))
    )
    (net (code "36") (name "Net-(J1-Pad13)") (class "Default")
      (node (ref "J1") (pin "13") (pinfunction "13_13") (pintype "bidirectional"))
      (node (ref "L1") (pin "2") (pinfunction "2_2") (pintype "passive"))
    )
    (net (code "37") (name "Net-(J1-Pad14)") (class "Default")
      (node (ref "J1") (pin "14") (pinfunction "14_14") (pintype "bidirectional"))
      (node (ref "L7") (pin "2") (pinfunction "2_2") (pintype "passive"))
    )
    (net (code "38") (name "Net-(J7-Pad8)") (class "Default")
      (node (ref "J7") (pin "8") (pinfunction "8_8") (pintype "bidirectional"))
      (node (ref "R1") (pin "2") (pinfunction "2_2") (pintype "passive"))
    )
    (net (code "39") (name "Net-(U1-AIN)") (class "Default")
      (node (ref "C23") (pin "2") (pinfunction "2_2") (pintype "passive"))
      (node (ref "R3") (pin "1") (pinfunction "1_1") (pintype "passive"))
      (node (ref "U1") (pin "3") (pinfunction "AIN_3") (pintype "input"))
    )
    (net (code "40") (name "Net-(U2-VREFIN{slash}VREFOUT)") (class "Default")
      (node (ref "C22") (pin "2") (pinfunction "2_2") (pintype "passive"))
      (node (ref "U2") (pin "10") (pinfunction "VREFIN/VREFOUT_10") (pintype "bidirectional"))
    )
    (net (code "41") (name "P3V3") (class "Default")
      (node (ref "C11") (pin "2") (pinfunction "2_2") (pintype "passive"))
      (node (ref "C15") (pin "2") (pinfunction "2_2") (pintype "passive"))
      (node (ref "C16") (pin "2") (pinfunction "2_2") (pintype "passive"))
      (node (ref "C17") (pin "2") (pinfunction "2_2") (pintype "passive"))
      (node (ref "C26") (pin "2") (pinfunction "2_2") (pintype "passive"))
      (node (ref "C27") (pin "2") (pinfunction "2_2") (pintype "passive"))
      (node (ref "C28") (pin "2") (pinfunction "2_2") (pintype "passive"))
      (node (ref "C6") (pin "2") (pinfunction "2_2") (pintype "passive"))
      (node (ref "C7") (pin "1") (pinfunction "1_1") (pintype "passive"))
      (node (ref "C8") (pin "2") (pinfunction "2_2") (pintype "passive"))
      (node (ref "C9") (pin "2") (pinfunction "2_2") (pintype "passive"))
      (node (ref "D1") (pin "4") (pinfunction "VCC_4") (pintype "power_in"))
      (node (ref "IC1") (pin "14") (pinfunction "VCC_14") (pintype "power_in"))
      (node (ref "IC10") (pin "5") (pinfunction "VCC_5") (pintype "power_in"))
      (node (ref "IC2") (pin "5") (pinfunction "VCC_5") (pintype "power_in"))
      (node (ref "IC3") (pin "4") (pinfunction "VCC_4") (pintype "power_in"))
      (node (ref "IC4") (pin "5") (pinfunction "VOUT_5") (pintype "power_in"))
      (node (ref "IC5") (pin "12") (pinfunction "K_12") (pintype "input"))
      (node (ref "IC5") (pin "14") (pinfunction "~{CLR}_14") (pintype "input"))
      (node (ref "IC5") (pin "15") (pinfunction "~{CLR}_15") (pintype "input"))
      (node (ref "IC5") (pin "16") (pinfunction "VCC_16") (pintype "power_in"))
      (node (ref "IC5") (pin "2") (pinfunction "K_2") (pintype "input"))
      (node (ref "IC8") (pin "5") (pinfunction "VCC_5") (pintype "power_in"))
      (node (ref "J8") (pin "5") (pinfunction "5_5") (pintype "bidirectional"))
      (node (ref "J9") (pin "7") (pinfunction "7_7") (pintype "bidirectional"))
      (node (ref "U1") (pin "1") (pinfunction "VDD_1") (pintype "power_in"))
      (node (ref "U2") (pin "5") (pinfunction "~{CLR}_5") (pintype "input"))
      (node (ref "U2") (pin "9") (pinfunction "VDD_9") (pintype "power_in"))
    )
    (net (code "42") (name "P5V0MP") (class "Default")
      (node (ref "C12") (pin "2") (pinfunction "2_2") (pintype "passive"))
      (node (ref "C2") (pin "2") (pinfunction "2_2") (pintype "passive"))
      (node (ref "C5") (pin "2") (pinfunction "2_2") (pintype "passive"))
      (node (ref "IC4") (pin "1") (pinfunction "VIN_1") (pintype "input"))
      (node (ref "IC4") (pin "3") (pinfunction "EN_3") (pintype "input"))
      (node (ref "IC6") (pin "5") (pinfunction "VCC_5") (pintype "power_in"))
      (node (ref "IC7") (pin "5") (pinfunction "VCC_5") (pintype "power_in"))
      (node (ref "L1") (pin "1") (pinfunction "1_1") (pintype "passive"))
      (node (ref "TP1") (pin "1") (pinfunction "1_1") (pintype "bidirectional"))
    )
    (net (code "43") (name "VCC_PREAMP") (class "Default")
      (node (ref "C4") (pin "2") (pinfunction "2_2") (pintype "passive"))
      (node (ref "J6") (pin "7") (pinfunction "7_7") (pintype "bidirectional"))
      (node (ref "J7") (pin "1") (pinfunction "1_1") (pintype "bidirectional"))
      (node (ref "L4") (pin "2") (pinfunction "2_2") (pintype "passive"))
    )
    (net (code "44") (name "VCC_PWRAMP") (class "Default")
      (node (ref "C13") (pin "1") (pinfunction "1_1") (pintype "passive"))
      (node (ref "C14") (pin "2") (pinfunction "2_2") (pintype "passive"))
      (node (ref "C3") (pin "2") (pinfunction "2_2") (pintype "passive"))
      (node (ref "J8") (pin "1") (pinfunction "1_1") (pintype "bidirectional"))
      (node (ref "J8") (pin "3") (pinfunction "3_3") (pintype "bidirectional"))
      (node (ref "L2") (pin "2") (pinfunction "2_2") (pintype "passive"))
    )
    (net (code "45") (name "unconnected-(IC3-NC-Pad5)") (class "Default")
      (node (ref "IC3") (pin "5") (pinfunction "NC_5") (pintype "passive+no_connect"))
    )
    (net (code "46") (name "unconnected-(IC4-NC-Pad4)") (class "Default")
      (node (ref "IC4") (pin "4") (pinfunction "NC_4") (pintype "passive"))
    )
    (net (code "47") (name "unconnected-(IC5A-~{Q}-Pad6)") (class "Default")
      (node (ref "IC5") (pin "6") (pinfunction "~{Q}_6") (pintype "output"))
    )
    (net (code "48") (name "unconnected-(IC5B-~{Q}-Pad7)") (class "Default")
      (node (ref "IC5") (pin "7") (pinfunction "~{Q}_7") (pintype "output"))
    )
    (net (code "49") (name "unconnected-(J6-Pad1)") (class "Default")
      (node (ref "J6") (pin "1") (pinfunction "1_1") (pintype "bidirectional"))
    )
    (net (code "50") (name "unconnected-(J6-Pad2)") (class "Default")
      (node (ref "J6") (pin "2") (pinfunction "2_2") (pintype "bidirectional"))
    )
    (net (code "51") (name "unconnected-(J6-Pad3)") (class "Default")
      (node (ref "J6") (pin "3") (pinfunction "3_3") (pintype "bidirectional"))
    )
    (net (code "52") (name "unconnected-(J6-Pad4)") (class "Default")
      (node (ref "J6") (pin "4") (pinfunction "4_4") (pintype "bidirectional"))
    )
    (net (code "53") (name "unconnected-(J6-Pad5)") (class "Default")
      (node (ref "J6") (pin "5") (pinfunction "5_5") (pintype "bidirectional"))
    )
    (net (code "54") (name "unconnected-(J7-Pad3)") (class "Default")
      (node (ref "J7") (pin "3") (pinfunction "3_3") (pintype "bidirectional"))
    )
    (net (code "55") (name "unconnected-(J7-Pad4)") (class "Default")
      (node (ref "J7") (pin "4") (pinfunction "4_4") (pintype "bidirectional"))
    )
    (net (code "56") (name "unconnected-(J7-Pad5)") (class "Default")
      (node (ref "J7") (pin "5") (pinfunction "5_5") (pintype "bidirectional"))
    )
    (net (code "57") (name "unconnected-(J7-Pad6)") (class "Default")
      (node (ref "J7") (pin "6") (pinfunction "6_6") (pintype "bidirectional"))
    )
    (net (code "58") (name "unconnected-(J8-Pad6)") (class "Default")
      (node (ref "J8") (pin "6") (pinfunction "6_6") (pintype "bidirectional"))
    )
    (net (code "59") (name "unconnected-(J9-Pad3)") (class "Default")
      (node (ref "J9") (pin "3") (pinfunction "3_3") (pintype "bidirectional"))
    )
    (net (code "60") (name "unconnected-(J9-Pad5)") (class "Default")
      (node (ref "J9") (pin "5") (pinfunction "5_5") (pintype "bidirectional"))
    )
    (net (code "61") (name "unconnected-(U2-ADDR-Pad6)") (class "Default")
      (node (ref "U2") (pin "6") (pinfunction "ADDR_6") (pintype "input+no_connect"))
    )
  )
)
